# Program_Counter.net
KiCad netlist of a schematic drawn in EAGLE
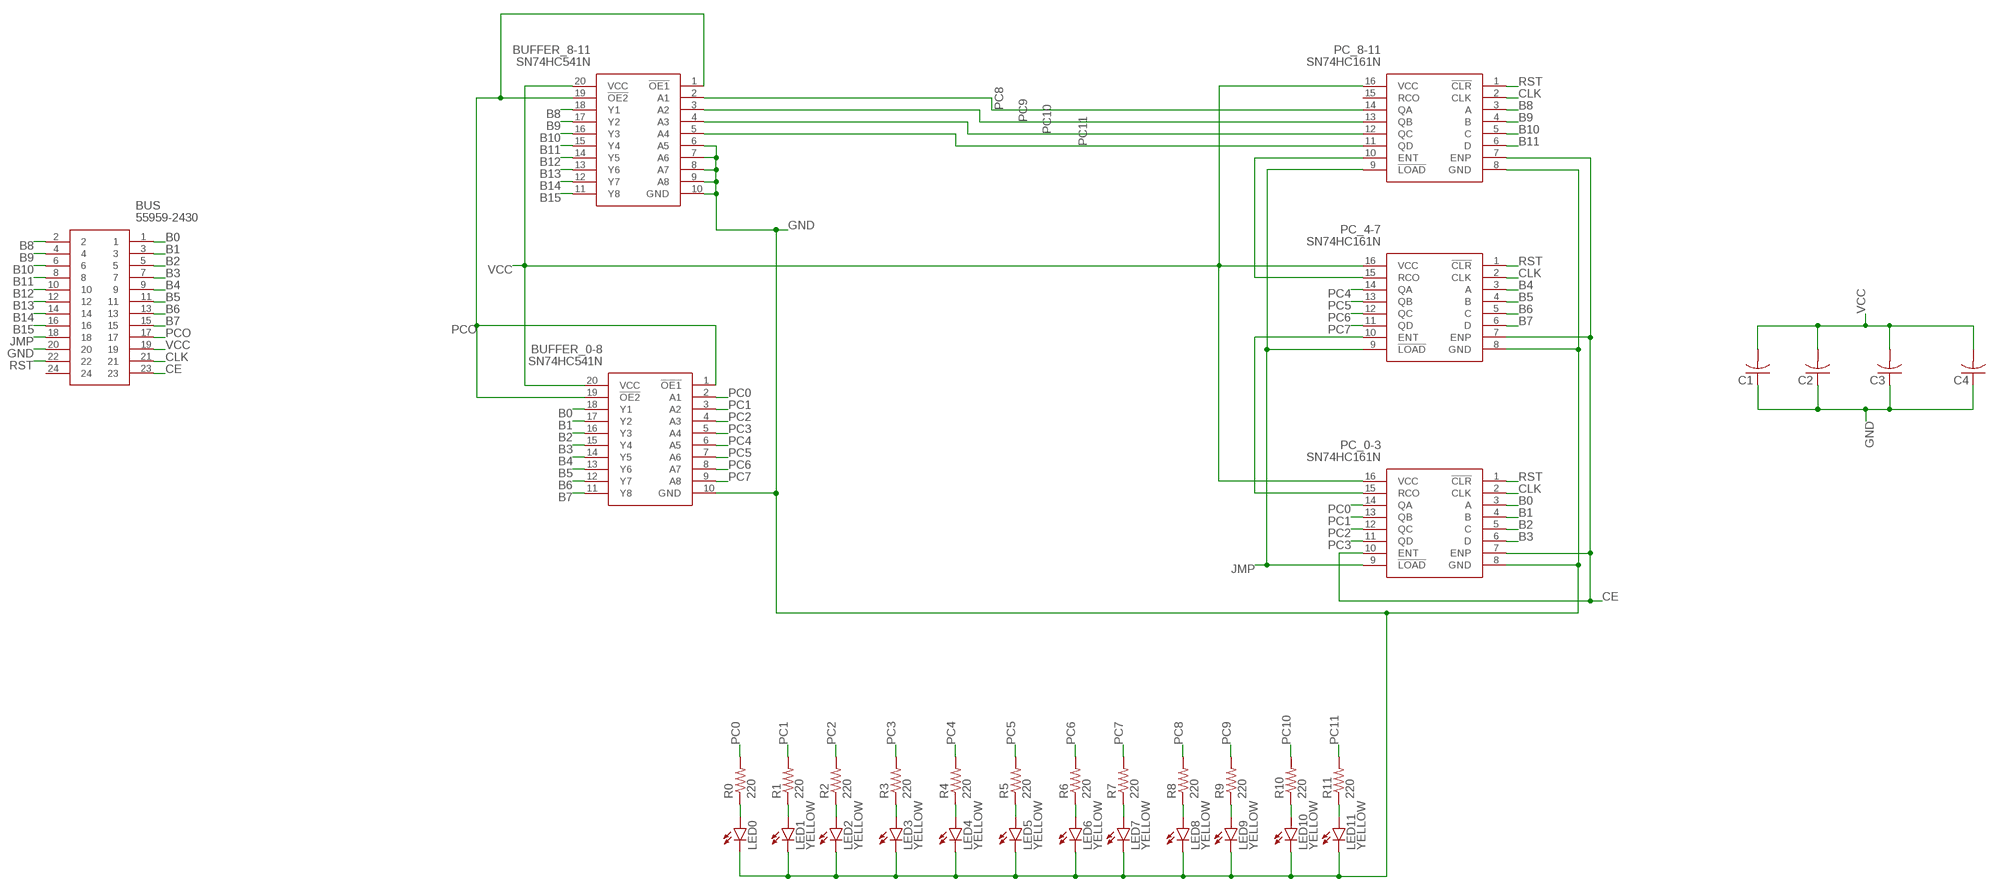
[diagram p0: schematic, sheet 1]

(export (version "E")
  (design (tool "Eeschema 10.0.6"))
  (components
    (comp (ref "BUFFER_0-8")
      (value "SN74HC541N")
      (footprint "eagle-import:DIP794W53P254L2540H508Q20N")
      (fields (field (name "MOUSER_PART_NUMBER") "595-SN74HC541N"))
      (libsource (lib "eagle-import") (part "SN74HC541N"))
    )
    (comp (ref "BUFFER_8-11")
      (value "SN74HC541N")
      (footprint "eagle-import:DIP794W53P254L2540H508Q20N")
      (fields (field (name "MOUSER_PART_NUMBER") "595-SN74HC541N"))
      (libsource (lib "eagle-import") (part "SN74HC541N"))
    )
    (comp (ref "BUS")
      (value "55959-2430")
      (footprint "eagle-import:559592430")
      (fields (field (name "MOUSER_PART_NUMBER") "538-55959-2430"))
      (libsource (lib "eagle-import") (part "55959-2430"))
    )
    (comp (ref "C1")
      (value "C-US025-024X044")
      (footprint "eagle-import:C025-024X044")
      (libsource (lib "eagle-import") (part "C-US025-024X044"))
    )
    (comp (ref "C2")
      (value "C-US025-024X044")
      (footprint "eagle-import:C025-024X044")
      (libsource (lib "eagle-import") (part "C-US025-024X044"))
    )
    (comp (ref "C3")
      (value "C-US025-024X044")
      (footprint "eagle-import:C025-024X044")
      (libsource (lib "eagle-import") (part "C-US025-024X044"))
    )
    (comp (ref "C4")
      (value "C-US025-024X044")
      (footprint "eagle-import:C025-024X044")
      (libsource (lib "eagle-import") (part "C-US025-024X044"))
    )
    (comp (ref "LED0")
      (value "LED3MM")
      (footprint "eagle-import:LED3MM")
      (libsource (lib "eagle-import") (part "LED3MM"))
    )
    (comp (ref "LED1")
      (value "YELLOW")
      (footprint "eagle-import:LED3MM")
      (libsource (lib "eagle-import") (part "LED3MM"))
    )
    (comp (ref "LED2")
      (value "YELLOW")
      (footprint "eagle-import:LED3MM")
      (libsource (lib "eagle-import") (part "LED3MM"))
    )
    (comp (ref "LED3")
      (value "YELLOW")
      (footprint "eagle-import:LED3MM")
      (libsource (lib "eagle-import") (part "LED3MM"))
    )
    (comp (ref "LED4")
      (value "YELLOW")
      (footprint "eagle-import:LED3MM")
      (libsource (lib "eagle-import") (part "LED3MM"))
    )
    (comp (ref "LED5")
      (value "YELLOW")
      (footprint "eagle-import:LED3MM")
      (libsource (lib "eagle-import") (part "LED3MM"))
    )
    (comp (ref "LED6")
      (value "YELLOW")
      (footprint "eagle-import:LED3MM")
      (libsource (lib "eagle-import") (part "LED3MM"))
    )
    (comp (ref "LED7")
      (value "YELLOW")
      (footprint "eagle-import:LED3MM")
      (libsource (lib "eagle-import") (part "LED3MM"))
    )
    (comp (ref "LED8")
      (value "YELLOW")
      (footprint "eagle-import:LED3MM")
      (libsource (lib "eagle-import") (part "LED3MM"))
    )
    (comp (ref "LED9")
      (value "YELLOW")
      (footprint "eagle-import:LED3MM")
      (libsource (lib "eagle-import") (part "LED3MM"))
    )
    (comp (ref "LED10")
      (value "YELLOW")
      (footprint "eagle-import:LED3MM")
      (libsource (lib "eagle-import") (part "LED3MM"))
    )
    (comp (ref "LED11")
      (value "YELLOW")
      (footprint "eagle-import:LED3MM")
      (libsource (lib "eagle-import") (part "LED3MM"))
    )
    (comp (ref "PC_0-3")
      (value "SN74HC161N")
      (footprint "eagle-import:DIP794W53P254L1930H508Q16N")
      (fields (field (name "MOUSER_PART_NUMBER") "595-SN74HC161N"))
      (libsource (lib "eagle-import") (part "SN74HC161N"))
    )
    (comp (ref "PC_4-7")
      (value "SN74HC161N")
      (footprint "eagle-import:DIP794W53P254L1930H508Q16N")
      (fields (field (name "MOUSER_PART_NUMBER") "595-SN74HC161N"))
      (libsource (lib "eagle-import") (part "SN74HC161N"))
    )
    (comp (ref "PC_8-11")
      (value "SN74HC161N")
      (footprint "eagle-import:DIP794W53P254L1930H508Q16N")
      (fields (field (name "MOUSER_PART_NUMBER") "595-SN74HC161N"))
      (libsource (lib "eagle-import") (part "SN74HC161N"))
    )
    (comp (ref "R0")
      (value "220")
      (footprint "eagle-import:0204_7")
      (libsource (lib "eagle-import") (part "R-US_0204/7"))
    )
    (comp (ref "R1")
      (value "220")
      (footprint "eagle-import:0204_7")
      (libsource (lib "eagle-import") (part "R-US_0204/7"))
    )
    (comp (ref "R2")
      (value "220")
      (footprint "eagle-import:0204_7")
      (libsource (lib "eagle-import") (part "R-US_0204/7"))
    )
    (comp (ref "R3")
      (value "220")
      (footprint "eagle-import:0204_7")
      (libsource (lib "eagle-import") (part "R-US_0204/7"))
    )
    (comp (ref "R4")
      (value "220")
      (footprint "eagle-import:0204_7")
      (libsource (lib "eagle-import") (part "R-US_0204/7"))
    )
    (comp (ref "R5")
      (value "220")
      (footprint "eagle-import:0204_7")
      (libsource (lib "eagle-import") (part "R-US_0204/7"))
    )
    (comp (ref "R6")
      (value "220")
      (footprint "eagle-import:0204_7")
      (libsource (lib "eagle-import") (part "R-US_0204/7"))
    )
    (comp (ref "R7")
      (value "220")
      (footprint "eagle-import:0204_7")
      (libsource (lib "eagle-import") (part "R-US_0204/7"))
    )
    (comp (ref "R8")
      (value "220")
      (footprint "eagle-import:0204_7")
      (libsource (lib "eagle-import") (part "R-US_0204/7"))
    )
    (comp (ref "R9")
      (value "220")
      (footprint "eagle-import:0204_7")
      (libsource (lib "eagle-import") (part "R-US_0204/7"))
    )
    (comp (ref "R10")
      (value "220")
      (footprint "eagle-import:0204_7")
      (libsource (lib "eagle-import") (part "R-US_0204/7"))
    )
    (comp (ref "R11")
      (value "220")
      (footprint "eagle-import:0204_7")
      (libsource (lib "eagle-import") (part "R-US_0204/7"))
    )
  )
  (nets
    (net (code "1") (name "/B0") (class "Default")
      (node (ref "BUFFER_0-8") (pin "18") (pinfunction "Y1_18") (pintype "bidirectional"))
      (node (ref "BUS") (pin "1") (pinfunction "1_1") (pintype "bidirectional"))
      (node (ref "PC_0-3") (pin "3") (pinfunction "A_3") (pintype "bidirectional"))
    )
    (net (code "2") (name "/B1") (class "Default")
      (node (ref "BUFFER_0-8") (pin "17") (pinfunction "Y2_17") (pintype "bidirectional"))
      (node (ref "BUS") (pin "3") (pinfunction "3_3") (pintype "bidirectional"))
      (node (ref "PC_0-3") (pin "4") (pinfunction "B_4") (pintype "bidirectional"))
    )
    (net (code "3") (name "/B2") (class "Default")
      (node (ref "BUFFER_0-8") (pin "16") (pinfunction "Y3_16") (pintype "bidirectional"))
      (node (ref "BUS") (pin "5") (pinfunction "5_5") (pintype "bidirectional"))
      (node (ref "PC_0-3") (pin "5") (pinfunction "C_5") (pintype "bidirectional"))
    )
    (net (code "4") (name "/B3") (class "Default")
      (node (ref "BUFFER_0-8") (pin "15") (pinfunction "Y4_15") (pintype "bidirectional"))
      (node (ref "BUS") (pin "7") (pinfunction "7_7") (pintype "bidirectional"))
      (node (ref "PC_0-3") (pin "6") (pinfunction "D_6") (pintype "bidirectional"))
    )
    (net (code "5") (name "/B4") (class "Default")
      (node (ref "BUFFER_0-8") (pin "14") (pinfunction "Y5_14") (pintype "bidirectional"))
      (node (ref "BUS") (pin "9") (pinfunction "9_9") (pintype "bidirectional"))
      (node (ref "PC_4-7") (pin "3") (pinfunction "A_3") (pintype "bidirectional"))
    )
    (net (code "6") (name "/B5") (class "Default")
      (node (ref "BUFFER_0-8") (pin "13") (pinfunction "Y6_13") (pintype "bidirectional"))
      (node (ref "BUS") (pin "11") (pinfunction "11_11") (pintype "bidirectional"))
      (node (ref "PC_4-7") (pin "4") (pinfunction "B_4") (pintype "bidirectional"))
    )
    (net (code "7") (name "/B6") (class "Default")
      (node (ref "BUFFER_0-8") (pin "12") (pinfunction "Y7_12") (pintype "bidirectional"))
      (node (ref "BUS") (pin "13") (pinfunction "13_13") (pintype "bidirectional"))
      (node (ref "PC_4-7") (pin "5") (pinfunction "C_5") (pintype "bidirectional"))
    )
    (net (code "8") (name "/B7") (class "Default")
      (node (ref "BUFFER_0-8") (pin "11") (pinfunction "Y8_11") (pintype "bidirectional"))
      (node (ref "BUS") (pin "15") (pinfunction "15_15") (pintype "bidirectional"))
      (node (ref "PC_4-7") (pin "6") (pinfunction "D_6") (pintype "bidirectional"))
    )
    (net (code "9") (name "/B8") (class "Default")
      (node (ref "BUFFER_8-11") (pin "18") (pinfunction "Y1_18") (pintype "bidirectional"))
      (node (ref "BUS") (pin "2") (pinfunction "2_2") (pintype "bidirectional"))
      (node (ref "PC_8-11") (pin "3") (pinfunction "A_3") (pintype "bidirectional"))
    )
    (net (code "10") (name "/B9") (class "Default")
      (node (ref "BUFFER_8-11") (pin "17") (pinfunction "Y2_17") (pintype "bidirectional"))
      (node (ref "BUS") (pin "4") (pinfunction "4_4") (pintype "bidirectional"))
      (node (ref "PC_8-11") (pin "4") (pinfunction "B_4") (pintype "bidirectional"))
    )
    (net (code "11") (name "/B10") (class "Default")
      (node (ref "BUFFER_8-11") (pin "16") (pinfunction "Y3_16") (pintype "bidirectional"))
      (node (ref "BUS") (pin "6") (pinfunction "6_6") (pintype "bidirectional"))
      (node (ref "PC_8-11") (pin "5") (pinfunction "C_5") (pintype "bidirectional"))
    )
    (net (code "12") (name "/B11") (class "Default")
      (node (ref "BUFFER_8-11") (pin "15") (pinfunction "Y4_15") (pintype "bidirectional"))
      (node (ref "BUS") (pin "8") (pinfunction "8_8") (pintype "bidirectional"))
      (node (ref "PC_8-11") (pin "6") (pinfunction "D_6") (pintype "bidirectional"))
    )
    (net (code "13") (name "/B12") (class "Default")
      (node (ref "BUFFER_8-11") (pin "14") (pinfunction "Y5_14") (pintype "bidirectional"))
      (node (ref "BUS") (pin "10") (pinfunction "10_10") (pintype "bidirectional"))
    )
    (net (code "14") (name "/B13") (class "Default")
      (node (ref "BUFFER_8-11") (pin "13") (pinfunction "Y6_13") (pintype "bidirectional"))
      (node (ref "BUS") (pin "12") (pinfunction "12_12") (pintype "bidirectional"))
    )
    (net (code "15") (name "/B14") (class "Default")
      (node (ref "BUFFER_8-11") (pin "12") (pinfunction "Y7_12") (pintype "bidirectional"))
      (node (ref "BUS") (pin "14") (pinfunction "14_14") (pintype "bidirectional"))
    )
    (net (code "16") (name "/B15") (class "Default")
      (node (ref "BUFFER_8-11") (pin "11") (pinfunction "Y8_11") (pintype "bidirectional"))
      (node (ref "BUS") (pin "16") (pinfunction "16_16") (pintype "bidirectional"))
    )
    (net (code "17") (name "/CE") (class "Default")
      (node (ref "BUS") (pin "23") (pinfunction "23_23") (pintype "bidirectional"))
      (node (ref "PC_0-3") (pin "10") (pinfunction "ENT_10") (pintype "bidirectional"))
      (node (ref "PC_0-3") (pin "7") (pinfunction "ENP_7") (pintype "bidirectional"))
      (node (ref "PC_4-7") (pin "7") (pinfunction "ENP_7") (pintype "bidirectional"))
      (node (ref "PC_8-11") (pin "7") (pinfunction "ENP_7") (pintype "bidirectional"))
    )
    (net (code "18") (name "/CLK") (class "Default")
      (node (ref "BUS") (pin "21") (pinfunction "21_21") (pintype "bidirectional"))
      (node (ref "PC_0-3") (pin "2") (pinfunction "CLK_2") (pintype "bidirectional"))
      (node (ref "PC_4-7") (pin "2") (pinfunction "CLK_2") (pintype "bidirectional"))
      (node (ref "PC_8-11") (pin "2") (pinfunction "CLK_2") (pintype "bidirectional"))
    )
    (net (code "19") (name "/GND") (class "Default")
      (node (ref "BUFFER_0-8") (pin "10") (pinfunction "GND_10") (pintype "bidirectional"))
      (node (ref "BUFFER_8-11") (pin "10") (pinfunction "GND_10") (pintype "bidirectional"))
      (node (ref "BUFFER_8-11") (pin "6") (pinfunction "A5_6") (pintype "bidirectional"))
      (node (ref "BUFFER_8-11") (pin "7") (pinfunction "A6_7") (pintype "bidirectional"))
      (node (ref "BUFFER_8-11") (pin "8") (pinfunction "A7_8") (pintype "bidirectional"))
      (node (ref "BUFFER_8-11") (pin "9") (pinfunction "A8_9") (pintype "bidirectional"))
      (node (ref "BUS") (pin "20") (pinfunction "20_20") (pintype "bidirectional"))
      (node (ref "C1") (pin "1") (pinfunction "1_1") (pintype "passive"))
      (node (ref "C2") (pin "1") (pinfunction "1_1") (pintype "passive"))
      (node (ref "C3") (pin "1") (pinfunction "1_1") (pintype "passive"))
      (node (ref "C4") (pin "1") (pinfunction "1_1") (pintype "passive"))
      (node (ref "LED0") (pin "K") (pinfunction "C_K") (pintype "passive"))
      (node (ref "LED1") (pin "K") (pinfunction "C_K") (pintype "passive"))
      (node (ref "LED10") (pin "K") (pinfunction "C_K") (pintype "passive"))
      (node (ref "LED11") (pin "K") (pinfunction "C_K") (pintype "passive"))
      (node (ref "LED2") (pin "K") (pinfunction "C_K") (pintype "passive"))
      (node (ref "LED3") (pin "K") (pinfunction "C_K") (pintype "passive"))
      (node (ref "LED4") (pin "K") (pinfunction "C_K") (pintype "passive"))
      (node (ref "LED5") (pin "K") (pinfunction "C_K") (pintype "passive"))
      (node (ref "LED6") (pin "K") (pinfunction "C_K") (pintype "passive"))
      (node (ref "LED7") (pin "K") (pinfunction "C_K") (pintype "passive"))
      (node (ref "LED8") (pin "K") (pinfunction "C_K") (pintype "passive"))
      (node (ref "LED9") (pin "K") (pinfunction "C_K") (pintype "passive"))
      (node (ref "PC_0-3") (pin "8") (pinfunction "GND_8") (pintype "bidirectional"))
      (node (ref "PC_4-7") (pin "8") (pinfunction "GND_8") (pintype "bidirectional"))
      (node (ref "PC_8-11") (pin "8") (pinfunction "GND_8") (pintype "bidirectional"))
    )
    (net (code "20") (name "/JMP") (class "Default")
      (node (ref "BUS") (pin "18") (pinfunction "18_18") (pintype "bidirectional"))
      (node (ref "PC_0-3") (pin "9") (pinfunction "~{LOAD}_9") (pintype "bidirectional"))
      (node (ref "PC_4-7") (pin "9") (pinfunction "~{LOAD}_9") (pintype "bidirectional"))
      (node (ref "PC_8-11") (pin "9") (pinfunction "~{LOAD}_9") (pintype "bidirectional"))
    )
    (net (code "21") (name "/PC0") (class "Default")
      (node (ref "BUFFER_0-8") (pin "2") (pinfunction "A1_2") (pintype "bidirectional"))
      (node (ref "PC_0-3") (pin "14") (pinfunction "QA_14") (pintype "bidirectional"))
      (node (ref "R0") (pin "2") (pinfunction "2_2") (pintype "passive"))
    )
    (net (code "22") (name "/PC1") (class "Default")
      (node (ref "BUFFER_0-8") (pin "3") (pinfunction "A2_3") (pintype "bidirectional"))
      (node (ref "PC_0-3") (pin "13") (pinfunction "QB_13") (pintype "bidirectional"))
      (node (ref "R1") (pin "2") (pinfunction "2_2") (pintype "passive"))
    )
    (net (code "23") (name "/PC2") (class "Default")
      (node (ref "BUFFER_0-8") (pin "4") (pinfunction "A3_4") (pintype "bidirectional"))
      (node (ref "PC_0-3") (pin "12") (pinfunction "QC_12") (pintype "bidirectional"))
      (node (ref "R2") (pin "2") (pinfunction "2_2") (pintype "passive"))
    )
    (net (code "24") (name "/PC3") (class "Default")
      (node (ref "BUFFER_0-8") (pin "5") (pinfunction "A4_5") (pintype "bidirectional"))
      (node (ref "PC_0-3") (pin "11") (pinfunction "QD_11") (pintype "bidirectional"))
      (node (ref "R3") (pin "2") (pinfunction "2_2") (pintype "passive"))
    )
    (net (code "25") (name "/PC4") (class "Default")
      (node (ref "BUFFER_0-8") (pin "6") (pinfunction "A5_6") (pintype "bidirectional"))
      (node (ref "PC_4-7") (pin "14") (pinfunction "QA_14") (pintype "bidirectional"))
      (node (ref "R4") (pin "2") (pinfunction "2_2") (pintype "passive"))
    )
    (net (code "26") (name "/PC5") (class "Default")
      (node (ref "BUFFER_0-8") (pin "7") (pinfunction "A6_7") (pintype "bidirectional"))
      (node (ref "PC_4-7") (pin "13") (pinfunction "QB_13") (pintype "bidirectional"))
      (node (ref "R5") (pin "2") (pinfunction "2_2") (pintype "passive"))
    )
    (net (code "27") (name "/PC6") (class "Default")
      (node (ref "BUFFER_0-8") (pin "8") (pinfunction "A7_8") (pintype "bidirectional"))
      (node (ref "PC_4-7") (pin "12") (pinfunction "QC_12") (pintype "bidirectional"))
      (node (ref "R6") (pin "2") (pinfunction "2_2") (pintype "passive"))
    )
    (net (code "28") (name "/PC7") (class "Default")
      (node (ref "BUFFER_0-8") (pin "9") (pinfunction "A8_9") (pintype "bidirectional"))
      (node (ref "PC_4-7") (pin "11") (pinfunction "QD_11") (pintype "bidirectional"))
      (node (ref "R7") (pin "2") (pinfunction "2_2") (pintype "passive"))
    )
    (net (code "29") (name "/PC8") (class "Default")
      (node (ref "BUFFER_8-11") (pin "2") (pinfunction "A1_2") (pintype "bidirectional"))
      (node (ref "PC_8-11") (pin "14") (pinfunction "QA_14") (pintype "bidirectional"))
      (node (ref "R8") (pin "2") (pinfunction "2_2") (pintype "passive"))
    )
    (net (code "30") (name "/PC9") (class "Default")
      (node (ref "BUFFER_8-11") (pin "3") (pinfunction "A2_3") (pintype "bidirectional"))
      (node (ref "PC_8-11") (pin "13") (pinfunction "QB_13") (pintype "bidirectional"))
      (node (ref "R9") (pin "2") (pinfunction "2_2") (pintype "passive"))
    )
    (net (code "31") (name "/PC10") (class "Default")
      (node (ref "BUFFER_8-11") (pin "4") (pinfunction "A3_4") (pintype "bidirectional"))
      (node (ref "PC_8-11") (pin "12") (pinfunction "QC_12") (pintype "bidirectional"))
      (node (ref "R10") (pin "2") (pinfunction "2_2") (pintype "passive"))
    )
    (net (code "32") (name "/PC11") (class "Default")
      (node (ref "BUFFER_8-11") (pin "5") (pinfunction "A4_5") (pintype "bidirectional"))
      (node (ref "PC_8-11") (pin "11") (pinfunction "QD_11") (pintype "bidirectional"))
      (node (ref "R11") (pin "2") (pinfunction "2_2") (pintype "passive"))
    )
    (net (code "33") (name "/PCO") (class "Default")
      (node (ref "BUFFER_0-8") (pin "1") (pinfunction "~{OE1}_1") (pintype "bidirectional"))
      (node (ref "BUFFER_0-8") (pin "19") (pinfunction "~{OE2}_19") (pintype "bidirectional"))
      (node (ref "BUFFER_8-11") (pin "1") (pinfunction "~{OE1}_1") (pintype "bidirectional"))
      (node (ref "BUFFER_8-11") (pin "19") (pinfunction "~{OE2}_19") (pintype "bidirectional"))
      (node (ref "BUS") (pin "17") (pinfunction "17_17") (pintype "bidirectional"))
    )
    (net (code "34") (name "/RST") (class "Default")
      (node (ref "BUS") (pin "22") (pinfunction "22_22") (pintype "bidirectional"))
      (node (ref "PC_0-3") (pin "1") (pinfunction "~{CLR}_1") (pintype "bidirectional"))
      (node (ref "PC_4-7") (pin "1") (pinfunction "~{CLR}_1") (pintype "bidirectional"))
      (node (ref "PC_8-11") (pin "1") (pinfunction "~{CLR}_1") (pintype "bidirectional"))
    )
    (net (code "35") (name "/VCC") (class "Default")
      (node (ref "BUFFER_0-8") (pin "20") (pinfunction "VCC_20") (pintype "bidirectional"))
      (node (ref "BUFFER_8-11") (pin "20") (pinfunction "VCC_20") (pintype "bidirectional"))
      (node (ref "BUS") (pin "19") (pinfunction "19_19") (pintype "bidirectional"))
      (node (ref "C1") (pin "2") (pinfunction "2_2") (pintype "passive"))
      (node (ref "C2") (pin "2") (pinfunction "2_2") (pintype "passive"))
      (node (ref "C3") (pin "2") (pinfunction "2_2") (pintype "passive"))
      (node (ref "C4") (pin "2") (pinfunction "2_2") (pintype "passive"))
      (node (ref "PC_0-3") (pin "16") (pinfunction "VCC_16") (pintype "bidirectional"))
      (node (ref "PC_4-7") (pin "16") (pinfunction "VCC_16") (pintype "bidirectional"))
      (node (ref "PC_8-11") (pin "16") (pinfunction "VCC_16") (pintype "bidirectional"))
    )
    (net (code "36") (name "Net-(LED0-PadA)") (class "Default")
      (node (ref "LED0") (pin "A") (pinfunction "A_A") (pintype "passive"))
      (node (ref "R0") (pin "1") (pinfunction "1_1") (pintype "passive"))
    )
    (net (code "37") (name "Net-(LED1-PadA)") (class "Default")
      (node (ref "LED1") (pin "A") (pinfunction "A_A") (pintype "passive"))
      (node (ref "R1") (pin "1") (pinfunction "1_1") (pintype "passive"))
    )
    (net (code "38") (name "Net-(LED2-PadA)") (class "Default")
      (node (ref "LED2") (pin "A") (pinfunction "A_A") (pintype "passive"))
      (node (ref "R2") (pin "1") (pinfunction "1_1") (pintype "passive"))
    )
    (net (code "39") (name "Net-(LED3-PadA)") (class "Default")
      (node (ref "LED3") (pin "A") (pinfunction "A_A") (pintype "passive"))
      (node (ref "R3") (pin "1") (pinfunction "1_1") (pintype "passive"))
    )
    (net (code "40") (name "Net-(LED4-PadA)") (class "Default")
      (node (ref "LED4") (pin "A") (pinfunction "A_A") (pintype "passive"))
      (node (ref "R4") (pin "1") (pinfunction "1_1") (pintype "passive"))
    )
    (net (code "41") (name "Net-(LED5-PadA)") (class "Default")
      (node (ref "LED5") (pin "A") (pinfunction "A_A") (pintype "passive"))
      (node (ref "R5") (pin "1") (pinfunction "1_1") (pintype "passive"))
    )
    (net (code "42") (name "Net-(LED6-PadA)") (class "Default")
      (node (ref "LED6") (pin "A") (pinfunction "A_A") (pintype "passive"))
      (node (ref "R6") (pin "1") (pinfunction "1_1") (pintype "passive"))
    )
    (net (code "43") (name "Net-(LED7-PadA)") (class "Default")
      (node (ref "LED7") (pin "A") (pinfunction "A_A") (pintype "passive"))
      (node (ref "R7") (pin "1") (pinfunction "1_1") (pintype "passive"))
    )
    (net (code "44") (name "Net-(LED8-PadA)") (class "Default")
      (node (ref "LED8") (pin "A") (pinfunction "A_A") (pintype "passive"))
      (node (ref "R8") (pin "1") (pinfunction "1_1") (pintype "passive"))
    )
    (net (code "45") (name "Net-(LED9-PadA)") (class "Default")
      (node (ref "LED9") (pin "A") (pinfunction "A_A") (pintype "passive"))
      (node (ref "R9") (pin "1") (pinfunction "1_1") (pintype "passive"))
    )
    (net (code "46") (name "Net-(LED10-PadA)") (class "Default")
      (node (ref "LED10") (pin "A") (pinfunction "A_A") (pintype "passive"))
      (node (ref "R10") (pin "1") (pinfunction "1_1") (pintype "passive"))
    )
    (net (code "47") (name "Net-(LED11-PadA)") (class "Default")
      (node (ref "LED11") (pin "A") (pinfunction "A_A") (pintype "passive"))
      (node (ref "R11") (pin "1") (pinfunction "1_1") (pintype "passive"))
    )
    (net (code "48") (name "Net-(PC_0-3-RCO)") (class "Default")
      (node (ref "PC_0-3") (pin "15") (pinfunction "RCO_15") (pintype "bidirectional"))
      (node (ref "PC_4-7") (pin "10") (pinfunction "ENT_10") (pintype "bidirectional"))
    )
    (net (code "49") (name "Net-(PC_4-7-RCO)") (class "Default")
      (node (ref "PC_4-7") (pin "15") (pinfunction "RCO_15") (pintype "bidirectional"))
      (node (ref "PC_8-11") (pin "10") (pinfunction "ENT_10") (pintype "bidirectional"))
    )
    (net (code "50") (name "unconnected-(BUS-Pad24)") (class "Default")
      (node (ref "BUS") (pin "24") (pinfunction "24_24") (pintype "bidirectional"))
    )
    (net (code "51") (name "unconnected-(PC_8-11-RCO-Pad15)") (class "Default")
      (node (ref "PC_8-11") (pin "15") (pinfunction "RCO_15") (pintype "bidirectional"))
    )
  )
)
